# final2.net
KiCad netlist of a schematic drawn in EAGLE
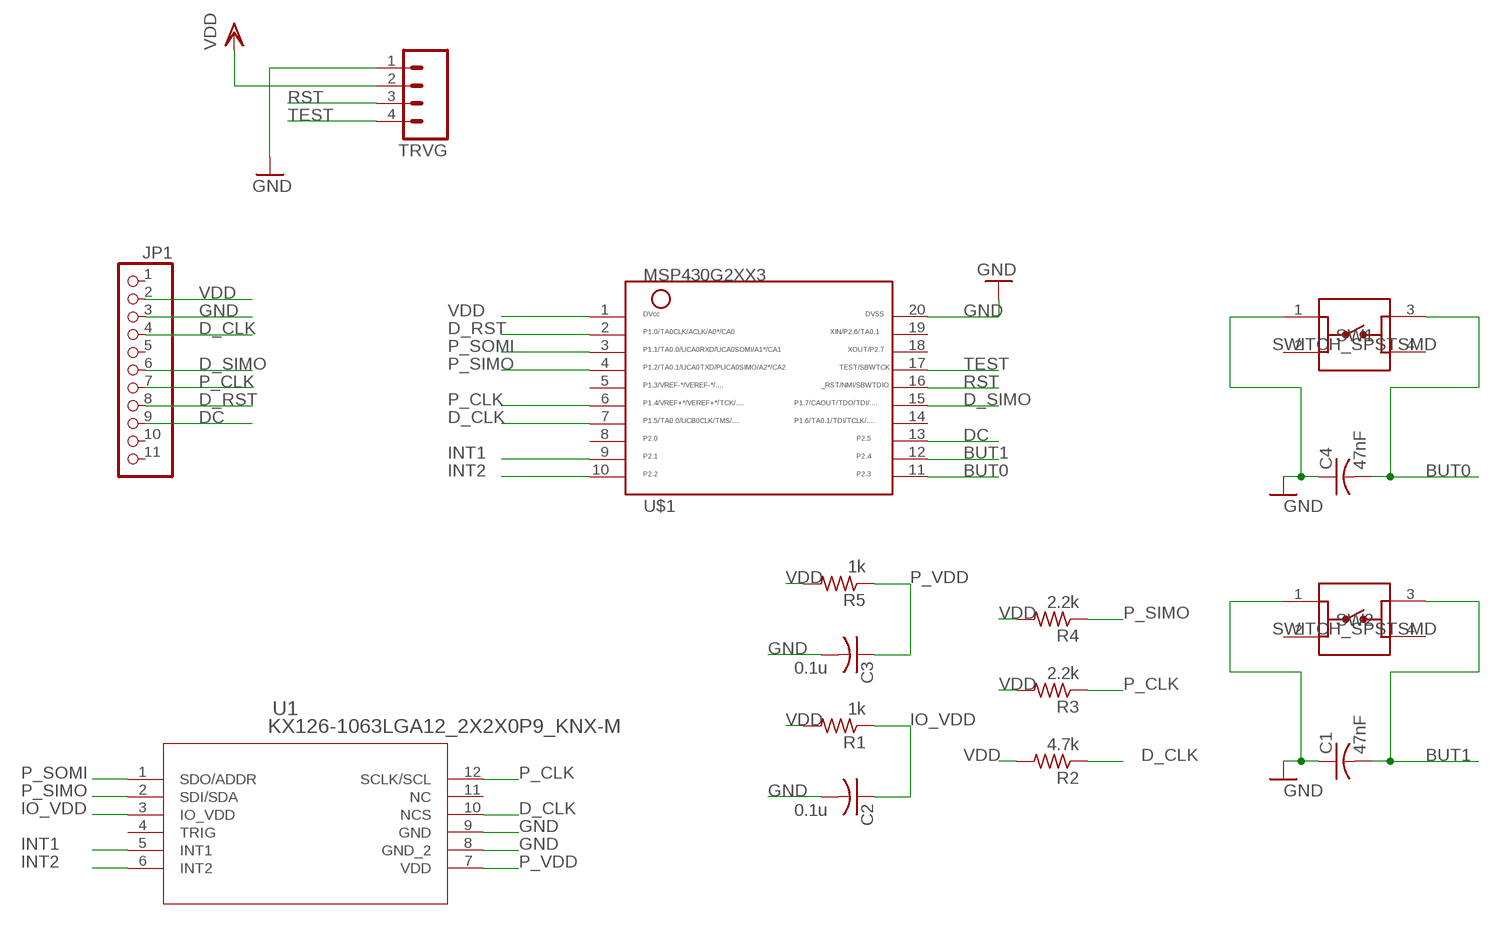
[diagram p0: schematic, sheet 1]

(export (version "E")
  (design (tool "Eeschema 10.0.6"))
  (components
    (comp (ref "C1")
      (value "47nF")
      (footprint "eagle-import:C0603")
      (libsource (lib "eagle-import") (part "C-USC0603"))
    )
    (comp (ref "C2")
      (value "0.1u")
      (footprint "eagle-import:C0603")
      (libsource (lib "eagle-import") (part "C-USC0603"))
    )
    (comp (ref "C3")
      (value "0.1u")
      (footprint "eagle-import:C0603")
      (libsource (lib "eagle-import") (part "C-USC0603"))
    )
    (comp (ref "C4")
      (value "47nF")
      (footprint "eagle-import:C0603")
      (libsource (lib "eagle-import") (part "C-USC0603"))
    )
    (comp (ref "JP1")
      (value "HEADER-1X11")
      (footprint "eagle-import:1X11_ROUND")
      (libsource (lib "eagle-import") (part "HEADER-1X11"))
    )
    (comp (ref "R1")
      (value "1k")
      (footprint "eagle-import:R0402")
      (libsource (lib "eagle-import") (part "R-US_R0402"))
    )
    (comp (ref "R2")
      (value "4.7k")
      (footprint "eagle-import:R0402")
      (libsource (lib "eagle-import") (part "R-US_R0402"))
    )
    (comp (ref "R3")
      (value "2.2k")
      (footprint "eagle-import:R0402")
      (libsource (lib "eagle-import") (part "R-US_R0402"))
    )
    (comp (ref "R4")
      (value "2.2k")
      (footprint "eagle-import:R0402")
      (libsource (lib "eagle-import") (part "R-US_R0402"))
    )
    (comp (ref "R5")
      (value "1k")
      (footprint "eagle-import:R0402")
      (libsource (lib "eagle-import") (part "R-US_R0402"))
    )
    (comp (ref "SW1")
      (value "SWITCH_SPSTSMD")
      (footprint "eagle-import:SW_1571563-4")
      (libsource (lib "eagle-import") (part "SWITCH_SPSTSMD"))
    )
    (comp (ref "SW2")
      (value "SWITCH_SPSTSMD")
      (footprint "eagle-import:SW_1571563-4")
      (libsource (lib "eagle-import") (part "SWITCH_SPSTSMD"))
    )
    (comp (ref "TRVG")
      (value "M04LOCK")
      (footprint "eagle-import:1X04_LOCK")
      (libsource (lib "eagle-import") (part "M04LOCK"))
    )
    (comp (ref "U$1")
      (value "MSP430G2XX3TSSOP")
      (footprint "eagle-import:PW20")
      (libsource (lib "eagle-import") (part "MSP430G2XX3TSSOP"))
    )
    (comp (ref "U1")
      (value "KX126-1063LGA12_2X2X0P9_KNX-M")
      (footprint "eagle-import:LGA12_2X2X0P9_KNX-M")
      (fields
        (field (name "MANUFACTURER_PART_NUMBER") "KX126-1063")
        (field (name "COPYRIGHT") "Copyright (C) 2021 Ultra Librarian. All rights reserved.")
      )
      (libsource (lib "eagle-import") (part "KX126-1063LGA12_2X2X0P9_KNX-M"))
    )
  )
  (nets
    (net (code "1") (name "/BUT0") (class "Default")
      (node (ref "C4") (pin "2") (pinfunction "2_2") (pintype "passive"))
      (node (ref "SW1") (pin "3") (pinfunction "3_3") (pintype "passive"))
      (node (ref "U$1") (pin "11") (pinfunction "11_11") (pintype "bidirectional"))
    )
    (net (code "2") (name "/BUT1") (class "Default")
      (node (ref "C1") (pin "2") (pinfunction "2_2") (pintype "passive"))
      (node (ref "SW2") (pin "3") (pinfunction "3_3") (pintype "passive"))
      (node (ref "U$1") (pin "12") (pinfunction "12_12") (pintype "bidirectional"))
    )
    (net (code "3") (name "/DC") (class "Default")
      (node (ref "JP1") (pin "9") (pinfunction "9_9") (pintype "passive"))
      (node (ref "U$1") (pin "13") (pinfunction "13_13") (pintype "bidirectional"))
    )
    (net (code "4") (name "/D_CLK") (class "Default")
      (node (ref "JP1") (pin "4") (pinfunction "4_4") (pintype "passive"))
      (node (ref "R2") (pin "1") (pinfunction "1_1") (pintype "passive"))
      (node (ref "U$1") (pin "7") (pinfunction "7_7") (pintype "bidirectional"))
      (node (ref "U1") (pin "10") (pinfunction "NCS_10") (pintype "input"))
    )
    (net (code "5") (name "/D_RST") (class "Default")
      (node (ref "JP1") (pin "8") (pinfunction "8_8") (pintype "passive"))
      (node (ref "U$1") (pin "2") (pinfunction "2_2") (pintype "bidirectional"))
    )
    (net (code "6") (name "/D_SIMO") (class "Default")
      (node (ref "JP1") (pin "6") (pinfunction "6_6") (pintype "passive"))
      (node (ref "U$1") (pin "15") (pinfunction "15_15") (pintype "bidirectional"))
    )
    (net (code "7") (name "/INT1") (class "Default")
      (node (ref "U$1") (pin "9") (pinfunction "9_9") (pintype "bidirectional"))
      (node (ref "U1") (pin "5") (pinfunction "INT1_5") (pintype "output"))
    )
    (net (code "8") (name "/INT2") (class "Default")
      (node (ref "U$1") (pin "10") (pinfunction "10_10") (pintype "bidirectional"))
      (node (ref "U1") (pin "6") (pinfunction "INT2_6") (pintype "output"))
    )
    (net (code "9") (name "/IO_VDD") (class "Default")
      (node (ref "C2") (pin "1") (pinfunction "1_1") (pintype "passive"))
      (node (ref "R1") (pin "1") (pinfunction "1_1") (pintype "passive"))
      (node (ref "U1") (pin "3") (pinfunction "IO_VDD_3") (pintype "power_in"))
    )
    (net (code "10") (name "/P_CLK") (class "Default")
      (node (ref "JP1") (pin "7") (pinfunction "7_7") (pintype "passive"))
      (node (ref "R3") (pin "1") (pinfunction "1_1") (pintype "passive"))
      (node (ref "U$1") (pin "6") (pinfunction "6_6") (pintype "bidirectional"))
      (node (ref "U1") (pin "12") (pinfunction "SCLK/SCL_12") (pintype "input"))
    )
    (net (code "11") (name "/P_SIMO") (class "Default")
      (node (ref "R4") (pin "1") (pinfunction "1_1") (pintype "passive"))
      (node (ref "U$1") (pin "4") (pinfunction "4_4") (pintype "bidirectional"))
      (node (ref "U1") (pin "2") (pinfunction "SDI/SDA_2") (pintype "input"))
    )
    (net (code "12") (name "/P_SOMI") (class "Default")
      (node (ref "U$1") (pin "3") (pinfunction "3_3") (pintype "bidirectional"))
      (node (ref "U1") (pin "1") (pinfunction "SDO/ADDR_1") (pintype "input"))
    )
    (net (code "13") (name "/P_VDD") (class "Default")
      (node (ref "C3") (pin "1") (pinfunction "1_1") (pintype "passive"))
      (node (ref "R5") (pin "1") (pinfunction "1_1") (pintype "passive"))
      (node (ref "U1") (pin "7") (pinfunction "VDD_7") (pintype "power_in"))
    )
    (net (code "14") (name "/RST") (class "Default")
      (node (ref "TRVG") (pin "3") (pinfunction "3_3") (pintype "passive"))
      (node (ref "U$1") (pin "16") (pinfunction "16_16") (pintype "bidirectional"))
    )
    (net (code "15") (name "/TEST") (class "Default")
      (node (ref "TRVG") (pin "4") (pinfunction "4_4") (pintype "passive"))
      (node (ref "U$1") (pin "17") (pinfunction "17_17") (pintype "bidirectional"))
    )
    (net (code "16") (name "GND") (class "Default")
      (node (ref "C1") (pin "1") (pinfunction "1_1") (pintype "passive"))
      (node (ref "C2") (pin "2") (pinfunction "2_2") (pintype "passive"))
      (node (ref "C3") (pin "2") (pinfunction "2_2") (pintype "passive"))
      (node (ref "C4") (pin "1") (pinfunction "1_1") (pintype "passive"))
      (node (ref "JP1") (pin "3") (pinfunction "3_3") (pintype "passive"))
      (node (ref "SW1") (pin "1") (pinfunction "1_1") (pintype "passive"))
      (node (ref "SW2") (pin "1") (pinfunction "1_1") (pintype "passive"))
      (node (ref "TRVG") (pin "1") (pinfunction "1_1") (pintype "passive"))
      (node (ref "U$1") (pin "20") (pinfunction "20_20") (pintype "bidirectional"))
      (node (ref "U1") (pin "8") (pinfunction "GND_2_8") (pintype "passive"))
      (node (ref "U1") (pin "9") (pinfunction "GND_9") (pintype "passive"))
    )
    (net (code "17") (name "VDD") (class "Default")
      (node (ref "JP1") (pin "2") (pinfunction "2_2") (pintype "passive"))
      (node (ref "R1") (pin "2") (pinfunction "2_2") (pintype "passive"))
      (node (ref "R2") (pin "2") (pinfunction "2_2") (pintype "passive"))
      (node (ref "R3") (pin "2") (pinfunction "2_2") (pintype "passive"))
      (node (ref "R4") (pin "2") (pinfunction "2_2") (pintype "passive"))
      (node (ref "R5") (pin "2") (pinfunction "2_2") (pintype "passive"))
      (node (ref "TRVG") (pin "2") (pinfunction "2_2") (pintype "passive"))
      (node (ref "U$1") (pin "1") (pinfunction "1_1") (pintype "bidirectional"))
    )
    (net (code "18") (name "unconnected-(JP1-Pad1)") (class "Default")
      (node (ref "JP1") (pin "1") (pinfunction "1_1") (pintype "passive"))
    )
    (net (code "19") (name "unconnected-(JP1-Pad5)") (class "Default")
      (node (ref "JP1") (pin "5") (pinfunction "5_5") (pintype "passive"))
    )
    (net (code "20") (name "unconnected-(JP1-Pad10)") (class "Default")
      (node (ref "JP1") (pin "10") (pinfunction "10_10") (pintype "passive"))
    )
    (net (code "21") (name "unconnected-(JP1-Pad11)") (class "Default")
      (node (ref "JP1") (pin "11") (pinfunction "11_11") (pintype "passive"))
    )
    (net (code "22") (name "unconnected-(SW1-Pad2)") (class "Default")
      (node (ref "SW1") (pin "2") (pinfunction "2_2") (pintype "passive"))
    )
    (net (code "23") (name "unconnected-(SW1-Pad4)") (class "Default")
      (node (ref "SW1") (pin "4") (pinfunction "4_4") (pintype "passive"))
    )
    (net (code "24") (name "unconnected-(SW2-Pad2)") (class "Default")
      (node (ref "SW2") (pin "2") (pinfunction "2_2") (pintype "passive"))
    )
    (net (code "25") (name "unconnected-(SW2-Pad4)") (class "Default")
      (node (ref "SW2") (pin "4") (pinfunction "4_4") (pintype "passive"))
    )
    (net (code "26") (name "unconnected-(U$1-Pad5)") (class "Default")
      (node (ref "U$1") (pin "5") (pinfunction "5_5") (pintype "bidirectional"))
    )
    (net (code "27") (name "unconnected-(U$1-Pad8)") (class "Default")
      (node (ref "U$1") (pin "8") (pinfunction "8_8") (pintype "bidirectional"))
    )
    (net (code "28") (name "unconnected-(U$1-Pad14)") (class "Default")
      (node (ref "U$1") (pin "14") (pinfunction "14_14") (pintype "bidirectional"))
    )
    (net (code "29") (name "unconnected-(U$1-Pad18)") (class "Default")
      (node (ref "U$1") (pin "18") (pinfunction "18_18") (pintype "bidirectional"))
    )
    (net (code "30") (name "unconnected-(U$1-Pad19)") (class "Default")
      (node (ref "U$1") (pin "19") (pinfunction "19_19") (pintype "bidirectional"))
    )
    (net (code "31") (name "unconnected-(U1-NC-Pad11)") (class "Default")
      (node (ref "U1") (pin "11") (pinfunction "NC_11") (pintype "no_connect"))
    )
    (net (code "32") (name "unconnected-(U1-TRIG-Pad4)") (class "Default")
      (node (ref "U1") (pin "4") (pinfunction "TRIG_4") (pintype "input"))
    )
  )
)
